# CTRL_PANEL.net
KiCad netlist of a schematic drawn in EAGLE
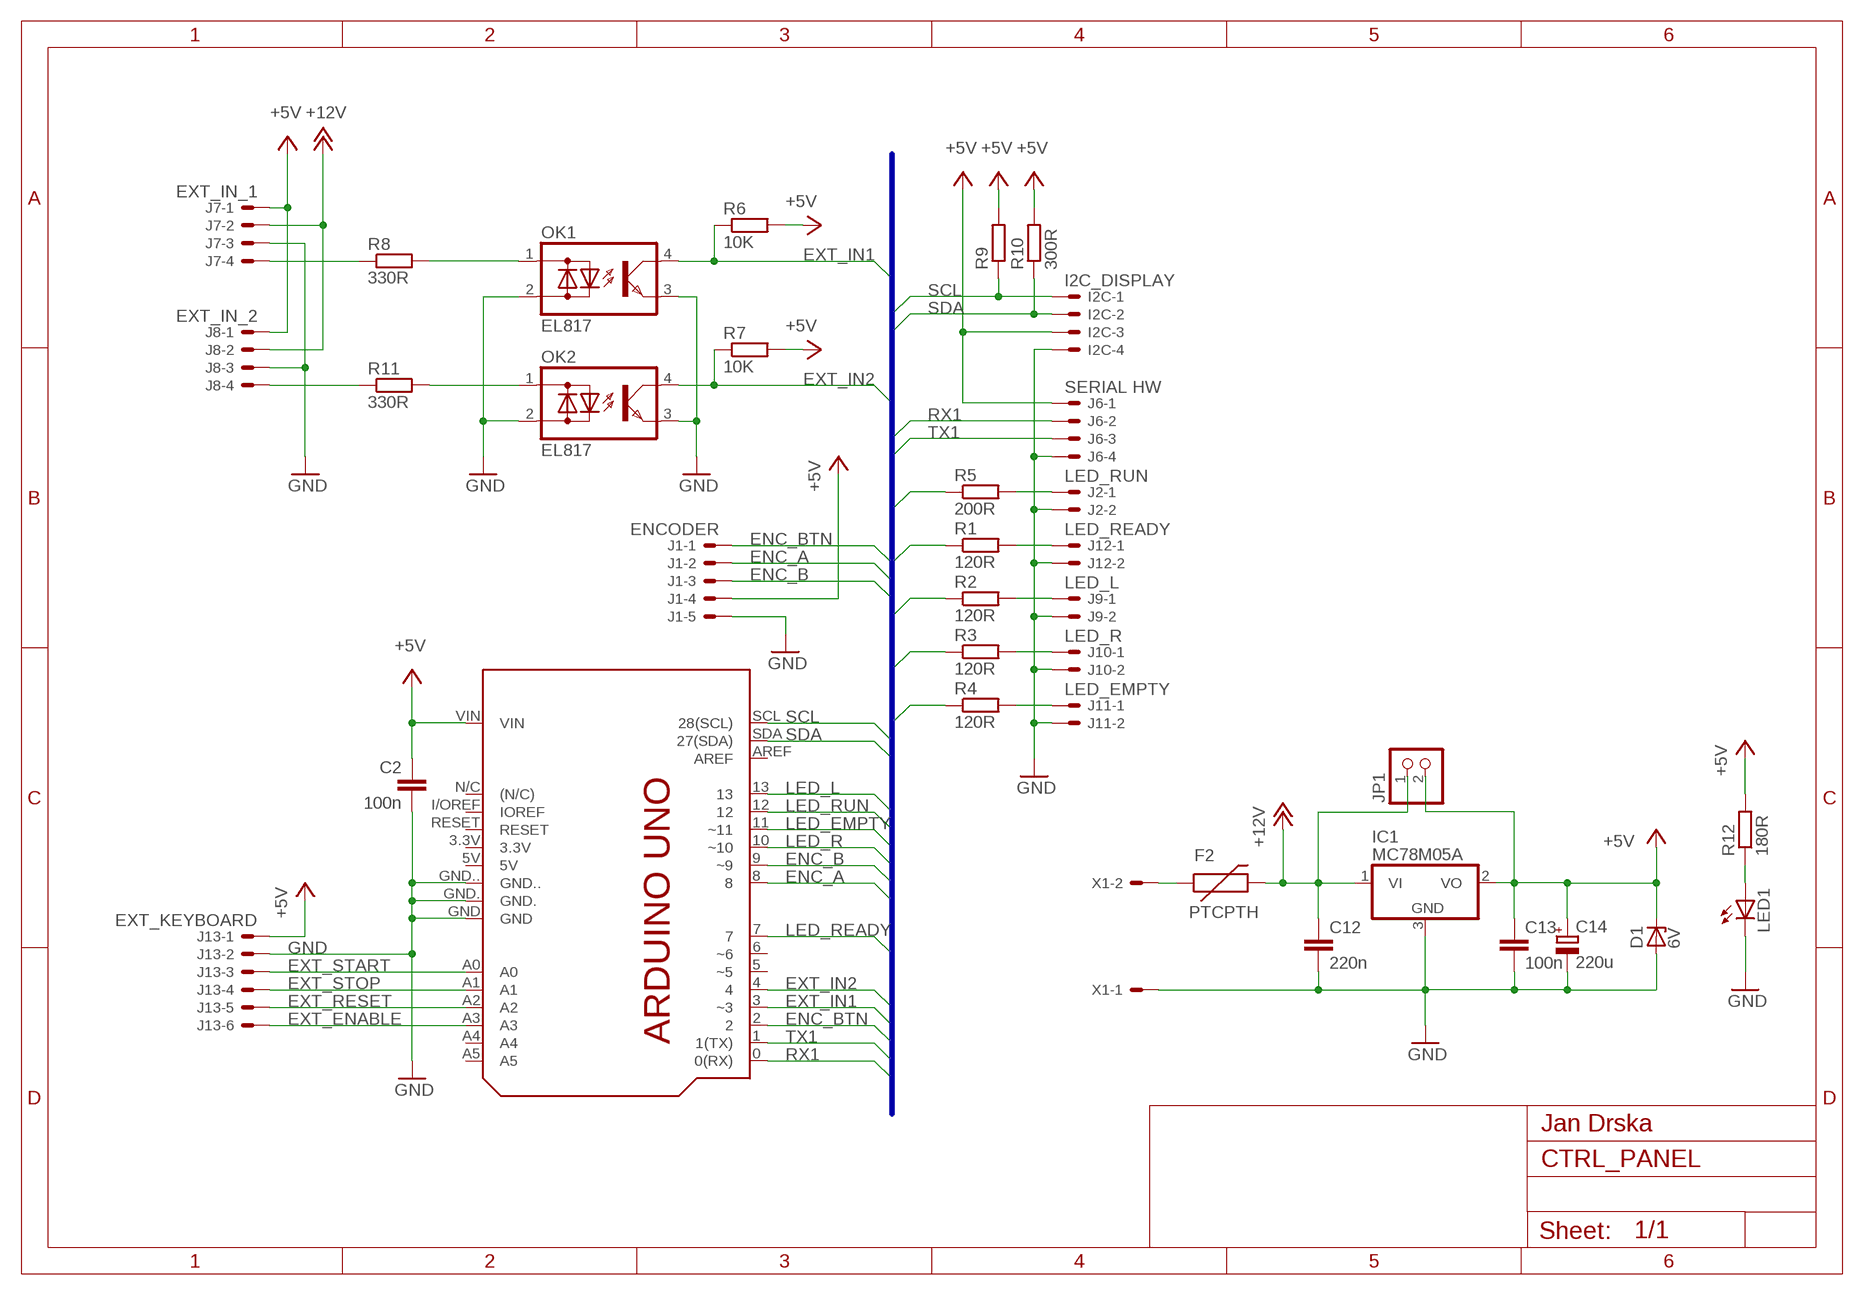
[diagram p0: schematic, sheet 1]

(export (version "E")
  (design (tool "Eeschema 10.0.6"))
  (components
    (comp (ref "C2")
      (value "100n")
      (footprint "eagle-import:C0603")
      (libsource (lib "eagle-import") (part "C-EUC0603"))
    )
    (comp (ref "C12")
      (value "220n")
      (footprint "eagle-import:C0603")
      (libsource (lib "eagle-import") (part "C-EUC0603"))
    )
    (comp (ref "C13")
      (value "100n")
      (footprint "eagle-import:C0603")
      (libsource (lib "eagle-import") (part "C-EUC0603"))
    )
    (comp (ref "C14")
      (value "220u")
      (footprint "eagle-import:E2,5-6E")
      (libsource (lib "eagle-import") (part "CPOL-EUE2,5-6E"))
    )
    (comp (ref "D1")
      (value "6V")
      (footprint "eagle-import:SMB")
      (libsource (lib "eagle-import") (part "ZENER-DIODESMB"))
    )
    (comp (ref "F2")
      (value "PTCPTH")
      (footprint "eagle-import:PTC")
      (libsource (lib "eagle-import") (part "PTCPTH"))
    )
    (comp (ref "I2C")
      (value "I2C_DISPLAY")
      (footprint "eagle-import:6410-04")
      (libsource (lib "eagle-import") (part "22-?-0427-2041"))
    )
    (comp (ref "IC1")
      (value "MC78M05A")
      (footprint "eagle-import:TO252")
      (libsource (lib "eagle-import") (part "78DT08"))
    )
    (comp (ref "J1")
      (value "ENCODER")
      (footprint "eagle-import:6410-05")
      (libsource (lib "eagle-import") (part "22-?-0527-2051"))
    )
    (comp (ref "J2")
      (value "LED_RUN")
      (footprint "eagle-import:6410-02")
      (libsource (lib "eagle-import") (part "22-?-0227-2021"))
    )
    (comp (ref "J6")
      (value "SERIAL HW")
      (footprint "eagle-import:6410-04")
      (libsource (lib "eagle-import") (part "22-?-0427-2041"))
    )
    (comp (ref "J7")
      (value "EXT_IN_1")
      (footprint "eagle-import:6410-04")
      (libsource (lib "eagle-import") (part "22-?-0427-2041"))
    )
    (comp (ref "J8")
      (value "EXT_IN_2")
      (footprint "eagle-import:6410-04")
      (libsource (lib "eagle-import") (part "22-?-0427-2041"))
    )
    (comp (ref "J9")
      (value "LED_L")
      (footprint "eagle-import:6410-02")
      (libsource (lib "eagle-import") (part "22-?-0227-2021"))
    )
    (comp (ref "J10")
      (value "LED_R")
      (footprint "eagle-import:6410-02")
      (libsource (lib "eagle-import") (part "22-?-0227-2021"))
    )
    (comp (ref "J11")
      (value "LED_EMPTY")
      (footprint "eagle-import:6410-02")
      (libsource (lib "eagle-import") (part "22-?-0227-2021"))
    )
    (comp (ref "J12")
      (value "LED_READY")
      (footprint "eagle-import:6410-02")
      (libsource (lib "eagle-import") (part "22-?-0227-2021"))
    )
    (comp (ref "J13")
      (value "EXT_KEYBOARD")
      (footprint "eagle-import:6410-06")
      (libsource (lib "eagle-import") (part "22-?-0627-2061"))
    )
    (comp (ref "JP1")
      (value "PINHD-1X2")
      (footprint "eagle-import:1X02")
      (libsource (lib "eagle-import") (part "PINHD-1X2"))
    )
    (comp (ref "LED1")
      (value "LEDCHIP-LED0603")
      (footprint "eagle-import:CHIP-LED0603")
      (libsource (lib "eagle-import") (part "LEDCHIP-LED0603"))
    )
    (comp (ref "OK1")
      (value "EL817")
      (footprint "eagle-import:DIL04")
      (libsource (lib "eagle-import") (part "PC814"))
    )
    (comp (ref "OK2")
      (value "EL817")
      (footprint "eagle-import:DIL04")
      (libsource (lib "eagle-import") (part "PC814"))
    )
    (comp (ref "PCB1")
      (value "ARDUINO_UNO")
      (footprint "eagle-import:ARDUINO_UNO")
      (libsource (lib "eagle-import") (part "ARDUINO_UNO"))
    )
    (comp (ref "R1")
      (value "120R")
      (footprint "eagle-import:R0603")
      (libsource (lib "eagle-import") (part "R-EU_R0603"))
    )
    (comp (ref "R2")
      (value "120R")
      (footprint "eagle-import:R0603")
      (libsource (lib "eagle-import") (part "R-EU_R0603"))
    )
    (comp (ref "R3")
      (value "120R")
      (footprint "eagle-import:R0603")
      (libsource (lib "eagle-import") (part "R-EU_R0603"))
    )
    (comp (ref "R4")
      (value "120R")
      (footprint "eagle-import:R0603")
      (libsource (lib "eagle-import") (part "R-EU_R0603"))
    )
    (comp (ref "R5")
      (value "200R")
      (footprint "eagle-import:R0603")
      (libsource (lib "eagle-import") (part "R-EU_R0603"))
    )
    (comp (ref "R6")
      (value "10K")
      (footprint "eagle-import:R0603")
      (libsource (lib "eagle-import") (part "R-EU_R0603"))
    )
    (comp (ref "R7")
      (value "10K")
      (footprint "eagle-import:R0603")
      (libsource (lib "eagle-import") (part "R-EU_R0603"))
    )
    (comp (ref "R8")
      (value "330R")
      (footprint "eagle-import:R0603")
      (libsource (lib "eagle-import") (part "R-EU_R0603"))
    )
    (comp (ref "R9")
      (value "R-EU_R0603")
      (footprint "eagle-import:R0603")
      (libsource (lib "eagle-import") (part "R-EU_R0603"))
    )
    (comp (ref "R10")
      (value "300R")
      (footprint "eagle-import:R0603")
      (libsource (lib "eagle-import") (part "R-EU_R0603"))
    )
    (comp (ref "R11")
      (value "330R")
      (footprint "eagle-import:R0603")
      (libsource (lib "eagle-import") (part "R-EU_R0603"))
    )
    (comp (ref "R12")
      (value "180R")
      (footprint "eagle-import:R0603")
      (libsource (lib "eagle-import") (part "R-EU_R0603"))
    )
    (comp (ref "X1")
      (value "22-23-2021")
      (footprint "eagle-import:22-23-2021")
      (fields (field (name "MF") "MOLEX"))
      (libsource (lib "eagle-import") (part "22-23-2021"))
    )
  )
  (nets
    (net (code "3") (name "+5V") (class "Default")
      (node (ref "C13") (pin "1") (pinfunction "1_1") (pintype "passive"))
      (node (ref "C14") (pin "+") (pinfunction "+_+") (pintype "passive"))
      (node (ref "C2") (pin "1") (pinfunction "1_1") (pintype "passive"))
      (node (ref "D1") (pin "C") (pinfunction "C_C") (pintype "passive"))
      (node (ref "I2C") (pin "3") (pinfunction "S_3") (pintype "passive"))
      (node (ref "IC1") (pin "2") (pinfunction "VO_2") (pintype "passive"))
      (node (ref "J1") (pin "4") (pinfunction "S_4") (pintype "passive"))
      (node (ref "J13") (pin "1") (pinfunction "S_1") (pintype "passive"))
      (node (ref "J6") (pin "1") (pinfunction "S_1") (pintype "passive"))
      (node (ref "J7") (pin "1") (pinfunction "S_1") (pintype "passive"))
      (node (ref "J8") (pin "1") (pinfunction "S_1") (pintype "passive"))
      (node (ref "JP1") (pin "2") (pinfunction "2_2") (pintype "passive"))
      (node (ref "PCB1") (pin "VIN") (pinfunction "VIN_VIN") (pintype "bidirectional"))
      (node (ref "R10") (pin "2") (pinfunction "2_2") (pintype "passive"))
      (node (ref "R12") (pin "2") (pinfunction "2_2") (pintype "passive"))
      (node (ref "R6") (pin "2") (pinfunction "2_2") (pintype "passive"))
      (node (ref "R7") (pin "2") (pinfunction "2_2") (pintype "passive"))
      (node (ref "R9") (pin "2") (pinfunction "2_2") (pintype "passive"))
    )
    (net (code "4") (name "+12V") (class "Default")
      (node (ref "C12") (pin "1") (pinfunction "1_1") (pintype "passive"))
      (node (ref "F2") (pin "P$2") (pinfunction "2_P$2") (pintype "bidirectional"))
      (node (ref "IC1") (pin "1") (pinfunction "VI_1") (pintype "input"))
      (node (ref "J7") (pin "2") (pinfunction "S_2") (pintype "passive"))
      (node (ref "J8") (pin "2") (pinfunction "S_2") (pintype "passive"))
      (node (ref "JP1") (pin "1") (pinfunction "1_1") (pintype "passive"))
    )
    (net (code "5") (name "/ENC_A") (class "Default")
      (node (ref "J1") (pin "2") (pinfunction "S_2") (pintype "passive"))
      (node (ref "PCB1") (pin "8") (pinfunction "8_8") (pintype "bidirectional"))
    )
    (net (code "6") (name "/ENC_B") (class "Default")
      (node (ref "J1") (pin "3") (pinfunction "S_3") (pintype "passive"))
      (node (ref "PCB1") (pin "9") (pinfunction "~{9}_9") (pintype "bidirectional"))
    )
    (net (code "7") (name "/ENC_BTN") (class "Default")
      (node (ref "J1") (pin "1") (pinfunction "S_1") (pintype "passive"))
      (node (ref "PCB1") (pin "2") (pinfunction "2_2") (pintype "bidirectional"))
    )
    (net (code "8") (name "/EXT_ENABLE") (class "Default")
      (node (ref "J13") (pin "6") (pinfunction "S_6") (pintype "passive"))
      (node (ref "PCB1") (pin "A3") (pinfunction "A3_A3") (pintype "bidirectional"))
    )
    (net (code "9") (name "/EXT_IN1") (class "Default")
      (node (ref "OK1") (pin "4") (pinfunction "C_4") (pintype "passive"))
      (node (ref "PCB1") (pin "3") (pinfunction "~{3}_3") (pintype "bidirectional"))
      (node (ref "R6") (pin "1") (pinfunction "1_1") (pintype "passive"))
    )
    (net (code "10") (name "/EXT_IN2") (class "Default")
      (node (ref "OK2") (pin "4") (pinfunction "C_4") (pintype "passive"))
      (node (ref "PCB1") (pin "4") (pinfunction "4_4") (pintype "bidirectional"))
      (node (ref "R7") (pin "1") (pinfunction "1_1") (pintype "passive"))
    )
    (net (code "11") (name "/EXT_RESET") (class "Default")
      (node (ref "J13") (pin "5") (pinfunction "S_5") (pintype "passive"))
      (node (ref "PCB1") (pin "A2") (pinfunction "A2_A2") (pintype "bidirectional"))
    )
    (net (code "12") (name "/EXT_START") (class "Default")
      (node (ref "J13") (pin "3") (pinfunction "S_3") (pintype "passive"))
      (node (ref "PCB1") (pin "A0") (pinfunction "A0_A0") (pintype "bidirectional"))
    )
    (net (code "13") (name "/EXT_STOP") (class "Default")
      (node (ref "J13") (pin "4") (pinfunction "S_4") (pintype "passive"))
      (node (ref "PCB1") (pin "A1") (pinfunction "A1_A1") (pintype "bidirectional"))
    )
    (net (code "14") (name "/LED_EMPTY") (class "Default")
      (node (ref "PCB1") (pin "11") (pinfunction "~{11}_11") (pintype "bidirectional"))
      (node (ref "R4") (pin "1") (pinfunction "1_1") (pintype "passive"))
    )
    (net (code "15") (name "/LED_L") (class "Default")
      (node (ref "PCB1") (pin "13") (pinfunction "13_13") (pintype "bidirectional"))
      (node (ref "R2") (pin "1") (pinfunction "1_1") (pintype "passive"))
    )
    (net (code "16") (name "/LED_R") (class "Default")
      (node (ref "PCB1") (pin "10") (pinfunction "~{10}_10") (pintype "bidirectional"))
      (node (ref "R3") (pin "1") (pinfunction "1_1") (pintype "passive"))
    )
    (net (code "17") (name "/LED_READY") (class "Default")
      (node (ref "PCB1") (pin "7") (pinfunction "7_7") (pintype "bidirectional"))
      (node (ref "R1") (pin "1") (pinfunction "1_1") (pintype "passive"))
    )
    (net (code "18") (name "/LED_RUN") (class "Default")
      (node (ref "PCB1") (pin "12") (pinfunction "12_12") (pintype "bidirectional"))
      (node (ref "R5") (pin "1") (pinfunction "1_1") (pintype "passive"))
    )
    (net (code "19") (name "/RX1") (class "Default")
      (node (ref "J6") (pin "2") (pinfunction "S_2") (pintype "passive"))
      (node (ref "PCB1") (pin "0") (pinfunction "0(RX)_0") (pintype "bidirectional"))
    )
    (net (code "20") (name "/SCL") (class "Default")
      (node (ref "I2C") (pin "1") (pinfunction "S_1") (pintype "passive"))
      (node (ref "PCB1") (pin "SCL") (pinfunction "28(SCL)_SCL") (pintype "bidirectional"))
      (node (ref "R9") (pin "1") (pinfunction "1_1") (pintype "passive"))
    )
    (net (code "21") (name "/SDA") (class "Default")
      (node (ref "I2C") (pin "2") (pinfunction "S_2") (pintype "passive"))
      (node (ref "PCB1") (pin "SDA") (pinfunction "27(SDA)_SDA") (pintype "bidirectional"))
      (node (ref "R10") (pin "1") (pinfunction "1_1") (pintype "passive"))
    )
    (net (code "22") (name "/TX1") (class "Default")
      (node (ref "J6") (pin "3") (pinfunction "S_3") (pintype "passive"))
      (node (ref "PCB1") (pin "1") (pinfunction "1(TX)_1") (pintype "bidirectional"))
    )
    (net (code "24") (name "GND") (class "Default")
      (node (ref "C12") (pin "2") (pinfunction "2_2") (pintype "passive"))
      (node (ref "C13") (pin "2") (pinfunction "2_2") (pintype "passive"))
      (node (ref "C14") (pin "-") (pinfunction "-_-") (pintype "passive"))
      (node (ref "C2") (pin "2") (pinfunction "2_2") (pintype "passive"))
      (node (ref "D1") (pin "A") (pinfunction "A_A") (pintype "passive"))
      (node (ref "I2C") (pin "4") (pinfunction "S_4") (pintype "passive"))
      (node (ref "IC1") (pin "3") (pinfunction "GND_3") (pintype "passive"))
      (node (ref "J1") (pin "5") (pinfunction "S_5") (pintype "passive"))
      (node (ref "J10") (pin "2") (pinfunction "S_2") (pintype "passive"))
      (node (ref "J11") (pin "2") (pinfunction "S_2") (pintype "passive"))
      (node (ref "J12") (pin "2") (pinfunction "S_2") (pintype "passive"))
      (node (ref "J13") (pin "2") (pinfunction "S_2") (pintype "passive"))
      (node (ref "J2") (pin "2") (pinfunction "S_2") (pintype "passive"))
      (node (ref "J6") (pin "4") (pinfunction "S_4") (pintype "passive"))
      (node (ref "J7") (pin "3") (pinfunction "S_3") (pintype "passive"))
      (node (ref "J8") (pin "3") (pinfunction "S_3") (pintype "passive"))
      (node (ref "J9") (pin "2") (pinfunction "S_2") (pintype "passive"))
      (node (ref "LED1") (pin "C") (pinfunction "C_C") (pintype "passive"))
      (node (ref "OK1") (pin "2") (pinfunction "AC2_2") (pintype "passive"))
      (node (ref "OK1") (pin "3") (pinfunction "E_3") (pintype "passive"))
      (node (ref "OK2") (pin "2") (pinfunction "AC2_2") (pintype "passive"))
      (node (ref "OK2") (pin "3") (pinfunction "E_3") (pintype "passive"))
      (node (ref "PCB1") (pin "GND") (pinfunction "GND_GND") (pintype "bidirectional"))
      (node (ref "PCB1") (pin "GND.") (pinfunction "GND._GND.") (pintype "bidirectional"))
      (node (ref "PCB1") (pin "GND..") (pinfunction "GND.._GND..") (pintype "bidirectional"))
      (node (ref "X1") (pin "1") (pinfunction "S_1") (pintype "passive"))
    )
    (net (code "25") (name "Net-(F2-1)") (class "Default")
      (node (ref "F2") (pin "P$1") (pinfunction "1_P$1") (pintype "bidirectional"))
      (node (ref "X1") (pin "2") (pinfunction "S_2") (pintype "passive"))
    )
    (net (code "26") (name "Net-(J2A-S)") (class "Default")
      (node (ref "J2") (pin "1") (pinfunction "S_1") (pintype "passive"))
      (node (ref "R5") (pin "2") (pinfunction "2_2") (pintype "passive"))
    )
    (net (code "27") (name "Net-(J7D-S)") (class "Default")
      (node (ref "J7") (pin "4") (pinfunction "S_4") (pintype "passive"))
      (node (ref "R8") (pin "1") (pinfunction "1_1") (pintype "passive"))
    )
    (net (code "28") (name "Net-(J8D-S)") (class "Default")
      (node (ref "J8") (pin "4") (pinfunction "S_4") (pintype "passive"))
      (node (ref "R11") (pin "1") (pinfunction "1_1") (pintype "passive"))
    )
    (net (code "29") (name "Net-(J9A-S)") (class "Default")
      (node (ref "J9") (pin "1") (pinfunction "S_1") (pintype "passive"))
      (node (ref "R2") (pin "2") (pinfunction "2_2") (pintype "passive"))
    )
    (net (code "30") (name "Net-(J10A-S)") (class "Default")
      (node (ref "J10") (pin "1") (pinfunction "S_1") (pintype "passive"))
      (node (ref "R3") (pin "2") (pinfunction "2_2") (pintype "passive"))
    )
    (net (code "31") (name "Net-(J11A-S)") (class "Default")
      (node (ref "J11") (pin "1") (pinfunction "S_1") (pintype "passive"))
      (node (ref "R4") (pin "2") (pinfunction "2_2") (pintype "passive"))
    )
    (net (code "32") (name "Net-(J12A-S)") (class "Default")
      (node (ref "J12") (pin "1") (pinfunction "S_1") (pintype "passive"))
      (node (ref "R1") (pin "2") (pinfunction "2_2") (pintype "passive"))
    )
    (net (code "33") (name "Net-(LED1-PadA)") (class "Default")
      (node (ref "LED1") (pin "A") (pinfunction "A_A") (pintype "passive"))
      (node (ref "R12") (pin "1") (pinfunction "1_1") (pintype "passive"))
    )
    (net (code "34") (name "Net-(OK1-AC1)") (class "Default")
      (node (ref "OK1") (pin "1") (pinfunction "AC1_1") (pintype "passive"))
      (node (ref "R8") (pin "2") (pinfunction "2_2") (pintype "passive"))
    )
    (net (code "35") (name "Net-(OK2-AC1)") (class "Default")
      (node (ref "OK2") (pin "1") (pinfunction "AC1_1") (pintype "passive"))
      (node (ref "R11") (pin "2") (pinfunction "2_2") (pintype "passive"))
    )
    (net (code "36") (name "unconnected-(PCB1-(N{slash}C)-PadN{slash}C)") (class "Default")
      (node (ref "PCB1") (pin "N/C") (pinfunction "(N/C)_N/C") (pintype "bidirectional"))
    )
    (net (code "37") (name "unconnected-(PCB1-IOREF-PadI{slash}OREF)") (class "Default")
      (node (ref "PCB1") (pin "I/OREF") (pinfunction "IOREF_I/OREF") (pintype "bidirectional"))
    )
    (net (code "38") (name "unconnected-(PCB1-Pad3.3V)") (class "Default")
      (node (ref "PCB1") (pin "3.3V") (pinfunction "3.3V_3.3V") (pintype "bidirectional"))
    )
    (net (code "39") (name "unconnected-(PCB1-Pad5V)") (class "Default")
      (node (ref "PCB1") (pin "5V") (pinfunction "5V_5V") (pintype "bidirectional"))
    )
    (net (code "40") (name "unconnected-(PCB1-PadA4)") (class "Default")
      (node (ref "PCB1") (pin "A4") (pinfunction "A4_A4") (pintype "bidirectional"))
    )
    (net (code "41") (name "unconnected-(PCB1-PadA5)") (class "Default")
      (node (ref "PCB1") (pin "A5") (pinfunction "A5_A5") (pintype "bidirectional"))
    )
    (net (code "42") (name "unconnected-(PCB1-PadAREF)") (class "Default")
      (node (ref "PCB1") (pin "AREF") (pinfunction "AREF_AREF") (pintype "bidirectional"))
    )
    (net (code "43") (name "unconnected-(PCB1-PadRESET)") (class "Default")
      (node (ref "PCB1") (pin "RESET") (pinfunction "RESET_RESET") (pintype "bidirectional"))
    )
    (net (code "44") (name "unconnected-(PCB1-~{5}-Pad5)") (class "Default")
      (node (ref "PCB1") (pin "5") (pinfunction "~{5}_5") (pintype "bidirectional"))
    )
    (net (code "45") (name "unconnected-(PCB1-~{6}-Pad6)") (class "Default")
      (node (ref "PCB1") (pin "6") (pinfunction "~{6}_6") (pintype "bidirectional"))
    )
  )
)
